# MCU_48pin.net
KiCad netlist of a schematic drawn in Altium Designer
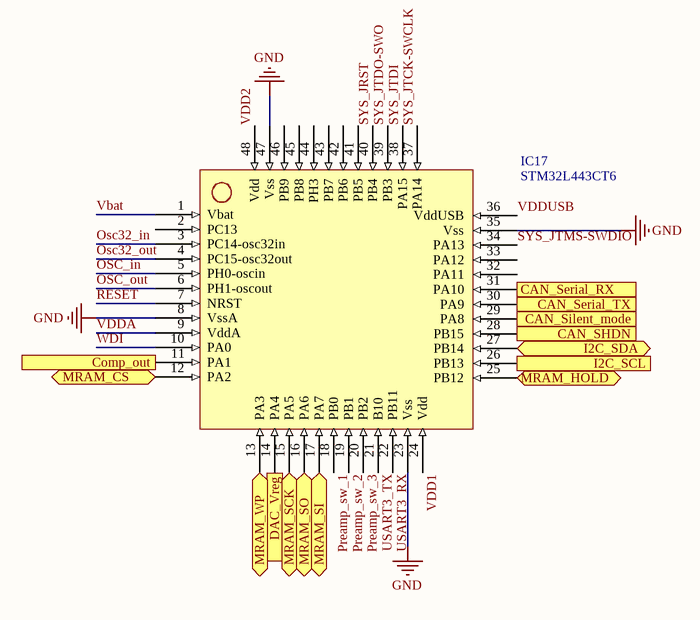
[diagram p0: MCU_48pin.SchDoc]

(export (version "E")
  (design (tool "Eeschema 10.0.6"))
  (components
    (comp (ref "IC17")
      (value "STM32L443CT6")
      (footprint "LQFP48")
      (description "Microcontroller STM32")
      (libsource (lib "Cubesat_lib") (part "STM32L443CT"))
    )
  )
  (nets
    (net (code "1") (name "/CAN_SHDN") (class "Default")
      (node (ref "IC17") (pin "28") (pinfunction "PB15_28") (pintype "input"))
    )
    (net (code "2") (name "/CAN_Serial_RX") (class "Default")
      (node (ref "IC17") (pin "31") (pinfunction "PA10_31") (pintype "input"))
    )
    (net (code "3") (name "/CAN_Serial_TX") (class "Default")
      (node (ref "IC17") (pin "30") (pinfunction "PA9_30") (pintype "input"))
    )
    (net (code "4") (name "/CAN_Silent_mode") (class "Default")
      (node (ref "IC17") (pin "29") (pinfunction "PA8_29") (pintype "input"))
    )
    (net (code "5") (name "/Comp_out") (class "Default")
      (node (ref "IC17") (pin "11") (pinfunction "PA1_11") (pintype "input"))
    )
    (net (code "6") (name "/DAC_Vreg") (class "Default")
      (node (ref "IC17") (pin "14") (pinfunction "PA4_14") (pintype "input"))
    )
    (net (code "7") (name "/I2C_SCL") (class "Default")
      (node (ref "IC17") (pin "26") (pinfunction "PB13_26") (pintype "input"))
    )
    (net (code "8") (name "/I2C_SDA") (class "Default")
      (node (ref "IC17") (pin "27") (pinfunction "PB14_27") (pintype "input"))
    )
    (net (code "9") (name "/MRAM_CS") (class "Default")
      (node (ref "IC17") (pin "12") (pinfunction "PA2_12") (pintype "input"))
    )
    (net (code "10") (name "/MRAM_HOLD") (class "Default")
      (node (ref "IC17") (pin "25") (pinfunction "PB12_25") (pintype "input"))
    )
    (net (code "11") (name "/MRAM_SCK") (class "Default")
      (node (ref "IC17") (pin "15") (pinfunction "PA5_15") (pintype "input"))
    )
    (net (code "12") (name "/MRAM_SI") (class "Default")
      (node (ref "IC17") (pin "17") (pinfunction "PA7_17") (pintype "input"))
    )
    (net (code "13") (name "/MRAM_SO") (class "Default")
      (node (ref "IC17") (pin "16") (pinfunction "PA6_16") (pintype "input"))
    )
    (net (code "14") (name "/MRAM_WP") (class "Default")
      (node (ref "IC17") (pin "13") (pinfunction "PA3_13") (pintype "input"))
    )
    (net (code "15") (name "/OSC_in") (class "Default")
      (node (ref "IC17") (pin "5") (pinfunction "PH0-oscin_5") (pintype "input"))
    )
    (net (code "16") (name "/OSC_out") (class "Default")
      (node (ref "IC17") (pin "6") (pinfunction "PH1-oscout_6") (pintype "input"))
    )
    (net (code "17") (name "/Osc32_in") (class "Default")
      (node (ref "IC17") (pin "3") (pinfunction "PC14-osc32in_3") (pintype "input"))
    )
    (net (code "18") (name "/Osc32_out") (class "Default")
      (node (ref "IC17") (pin "4") (pinfunction "PC15-osc32out_4") (pintype "input"))
    )
    (net (code "19") (name "/Preamp_sw_1") (class "Default")
      (node (ref "IC17") (pin "18") (pinfunction "PB0_18") (pintype "input"))
    )
    (net (code "20") (name "/Preamp_sw_2") (class "Default")
      (node (ref "IC17") (pin "19") (pinfunction "PB1_19") (pintype "input"))
    )
    (net (code "21") (name "/Preamp_sw_3") (class "Default")
      (node (ref "IC17") (pin "20") (pinfunction "PB2_20") (pintype "input"))
    )
    (net (code "22") (name "/RESET") (class "Default")
      (node (ref "IC17") (pin "7") (pinfunction "NRST_7") (pintype "input"))
    )
    (net (code "23") (name "/SYS_JRST") (class "Default")
      (node (ref "IC17") (pin "40") (pinfunction "PB4_40") (pintype "input"))
    )
    (net (code "24") (name "/SYS_JTCK-SWCLK") (class "Default")
      (node (ref "IC17") (pin "37") (pinfunction "PA14_37") (pintype "input"))
    )
    (net (code "25") (name "/SYS_JTDI") (class "Default")
      (node (ref "IC17") (pin "38") (pinfunction "PA15_38") (pintype "input"))
    )
    (net (code "26") (name "/SYS_JTDO-SWO") (class "Default")
      (node (ref "IC17") (pin "39") (pinfunction "PB3_39") (pintype "input"))
    )
    (net (code "27") (name "/SYS_JTMS-SWDIO") (class "Default")
      (node (ref "IC17") (pin "34") (pinfunction "PA13_34") (pintype "input"))
    )
    (net (code "28") (name "/USART3_RX") (class "Default")
      (node (ref "IC17") (pin "22") (pinfunction "PB11_22") (pintype "input"))
    )
    (net (code "29") (name "/USART3_TX") (class "Default")
      (node (ref "IC17") (pin "21") (pinfunction "B10_21") (pintype "input"))
    )
    (net (code "30") (name "/VDD1") (class "Default")
      (node (ref "IC17") (pin "24") (pinfunction "Vdd_24") (pintype "input"))
    )
    (net (code "31") (name "/VDD2") (class "Default")
      (node (ref "IC17") (pin "48") (pinfunction "Vdd_48") (pintype "input"))
    )
    (net (code "32") (name "/VDDA") (class "Default")
      (node (ref "IC17") (pin "9") (pinfunction "VddA_9") (pintype "input"))
    )
    (net (code "33") (name "/VDDUSB") (class "Default")
      (node (ref "IC17") (pin "36") (pinfunction "VddUSB_36") (pintype "input"))
    )
    (net (code "34") (name "/Vbat") (class "Default")
      (node (ref "IC17") (pin "1") (pinfunction "Vbat_1") (pintype "input"))
    )
    (net (code "35") (name "/WDI") (class "Default")
      (node (ref "IC17") (pin "10") (pinfunction "PA0_10") (pintype "input"))
    )
    (net (code "36") (name "GND") (class "Default")
      (node (ref "IC17") (pin "23") (pinfunction "Vss_23") (pintype "input"))
      (node (ref "IC17") (pin "35") (pinfunction "Vss_35") (pintype "input"))
      (node (ref "IC17") (pin "47") (pinfunction "Vss_47") (pintype "input"))
      (node (ref "IC17") (pin "8") (pinfunction "VssA_8") (pintype "input"))
    )
    (net (code "37") (name "unconnected-(IC17-PA11-Pad32)") (class "Default")
      (node (ref "IC17") (pin "32") (pinfunction "PA11_32") (pintype "input"))
    )
    (net (code "38") (name "unconnected-(IC17-PA12-Pad33)") (class "Default")
      (node (ref "IC17") (pin "33") (pinfunction "PA12_33") (pintype "input"))
    )
    (net (code "39") (name "unconnected-(IC17-PB5-Pad41)") (class "Default")
      (node (ref "IC17") (pin "41") (pinfunction "PB5_41") (pintype "input"))
    )
    (net (code "40") (name "unconnected-(IC17-PB6-Pad42)") (class "Default")
      (node (ref "IC17") (pin "42") (pinfunction "PB6_42") (pintype "input"))
    )
    (net (code "41") (name "unconnected-(IC17-PB7-Pad43)") (class "Default")
      (node (ref "IC17") (pin "43") (pinfunction "PB7_43") (pintype "input"))
    )
    (net (code "42") (name "unconnected-(IC17-PB8-Pad45)") (class "Default")
      (node (ref "IC17") (pin "45") (pinfunction "PB8_45") (pintype "input"))
    )
    (net (code "43") (name "unconnected-(IC17-PB9-Pad46)") (class "Default")
      (node (ref "IC17") (pin "46") (pinfunction "PB9_46") (pintype "input"))
    )
    (net (code "44") (name "unconnected-(IC17-PC13-Pad2)") (class "Default")
      (node (ref "IC17") (pin "2") (pinfunction "PC13_2") (pintype "input"))
    )
    (net (code "45") (name "unconnected-(IC17-PH3-Pad44)") (class "Default")
      (node (ref "IC17") (pin "44") (pinfunction "PH3_44") (pintype "input"))
    )
  )
)
